# MRCS-MorseKOB_Sounder_Driver.net
KiCad netlist of a schematic drawn in EAGLE
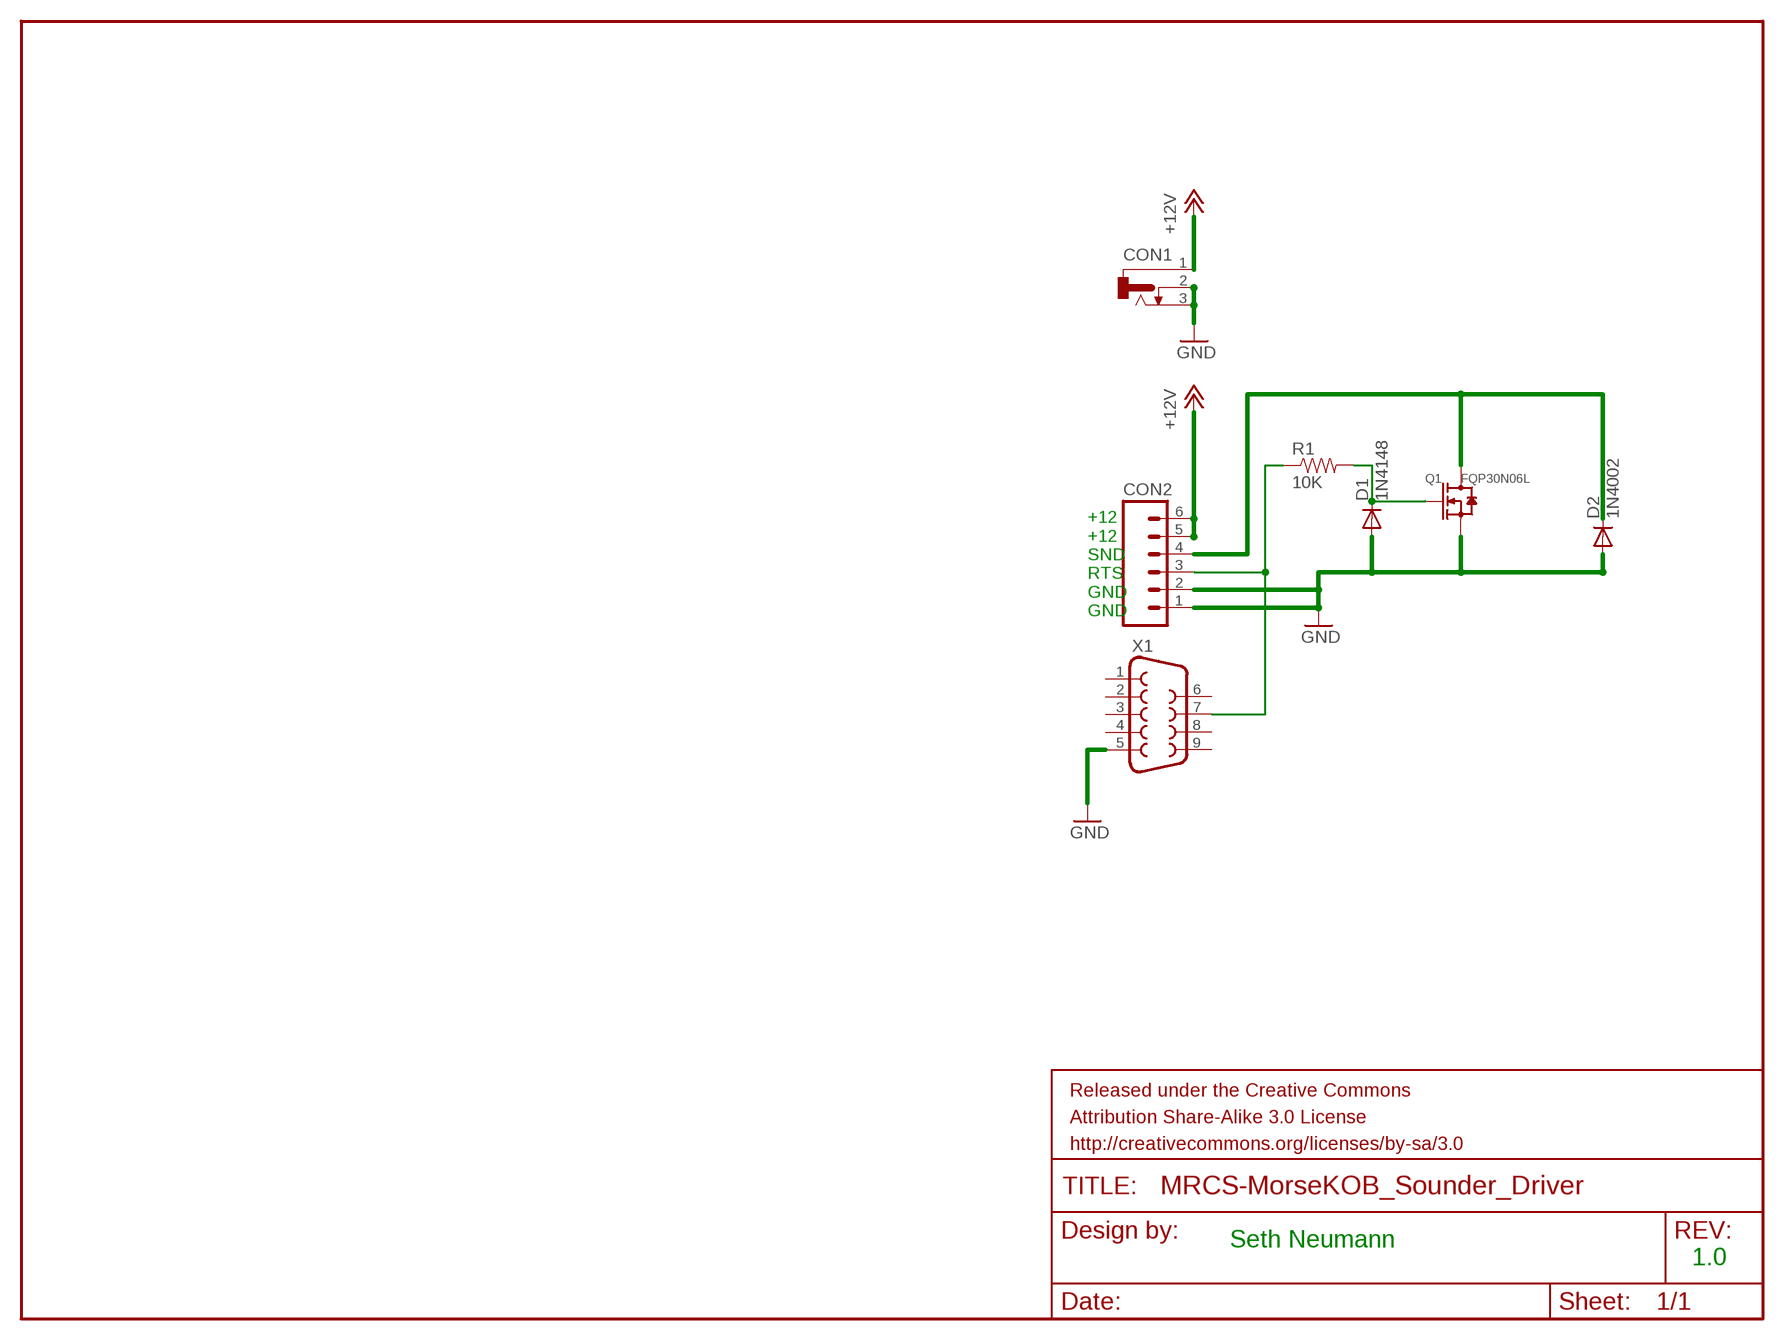
[diagram p0: schematic, sheet 1]

(export (version "E")
  (design (tool "Eeschema 10.0.6"))
  (components
    (comp (ref "CON1")
      (value "CONNECTOR-DC-POWER-RA")
      (footprint "eagle-import:DCJ0202")
      (libsource (lib "eagle-import") (part "CONNECTOR-DC-POWER-RA"))
    )
    (comp (ref "CON2")
      (value "CONNECTOR-M063.5MM-6")
      (footprint "eagle-import:SCREWTERMINAL-3.5MM-6")
      (libsource (lib "eagle-import") (part "CONNECTOR-M063.5MM-6"))
    )
    (comp (ref "D1")
      (value "1N4148")
      (footprint "eagle-import:DIODE-1N4148")
      (libsource (lib "eagle-import") (part "DIODE1N4148"))
    )
    (comp (ref "D2")
      (value "1N4002")
      (footprint "eagle-import:DIODE-1N4001")
      (libsource (lib "eagle-import") (part "DIODEPTH"))
    )
    (comp (ref "FRAME1")
      (value "FRAME-LETTER")
      (footprint "eagle-import:CREATIVE_COMMONS")
      (libsource (lib "eagle-import") (part "FRAME-LETTER"))
    )
    (comp (ref "Q1")
      (value "FQP30N06L")
      (footprint "eagle-import:TO220V")
      (libsource (lib "eagle-import") (part "MOSFET-N--?TO220V"))
    )
    (comp (ref "R1")
      (value "10K")
      (footprint "eagle-import:AXIAL-0.4-RES")
      (libsource (lib "eagle-import") (part "RPTH04"))
    )
    (comp (ref "X1")
      (value "DB9FEMALE")
      (footprint "eagle-import:DB9")
      (libsource (lib "eagle-import") (part "DB9FEMALE"))
    )
  )
  (nets
    (net (code "1") (name "+12V") (class "Default")
      (node (ref "CON1") (pin "1") (pinfunction "1_1") (pintype "passive"))
      (node (ref "CON2") (pin "5") (pinfunction "5_5") (pintype "passive"))
      (node (ref "CON2") (pin "6") (pinfunction "6_6") (pintype "passive"))
    )
    (net (code "2") (name "GND") (class "Default")
      (node (ref "CON1") (pin "2") (pinfunction "2_2") (pintype "passive"))
      (node (ref "CON1") (pin "3") (pinfunction "3_3") (pintype "passive"))
      (node (ref "CON2") (pin "1") (pinfunction "1_1") (pintype "passive"))
      (node (ref "CON2") (pin "2") (pinfunction "2_2") (pintype "passive"))
      (node (ref "D1") (pin "A") (pinfunction "A_A") (pintype "passive"))
      (node (ref "D2") (pin "A") (pinfunction "A_A") (pintype "passive"))
      (node (ref "Q1") (pin "3") (pinfunction "S_3") (pintype "passive"))
      (node (ref "X1") (pin "5") (pinfunction "5_5") (pintype "passive"))
    )
    (net (code "3") (name "Net-(Q1-D)") (class "Default")
      (node (ref "CON2") (pin "4") (pinfunction "4_4") (pintype "passive"))
      (node (ref "D2") (pin "C") (pinfunction "C_C") (pintype "passive"))
      (node (ref "Q1") (pin "2") (pinfunction "D_2") (pintype "passive"))
    )
    (net (code "4") (name "Net-(Q1-G)") (class "Default")
      (node (ref "D1") (pin "C") (pinfunction "C_C") (pintype "passive"))
      (node (ref "Q1") (pin "1") (pinfunction "G_1") (pintype "passive"))
      (node (ref "R1") (pin "P$2") (pinfunction "2_P$2") (pintype "passive"))
    )
    (net (code "5") (name "Net-(R1-1)") (class "Default")
      (node (ref "CON2") (pin "3") (pinfunction "3_3") (pintype "passive"))
      (node (ref "R1") (pin "P$1") (pinfunction "1_P$1") (pintype "passive"))
      (node (ref "X1") (pin "7") (pinfunction "7_7") (pintype "passive"))
    )
    (net (code "6") (name "unconnected-(X1-Pad1)") (class "Default")
      (node (ref "X1") (pin "1") (pinfunction "1_1") (pintype "passive"))
    )
    (net (code "7") (name "unconnected-(X1-Pad2)") (class "Default")
      (node (ref "X1") (pin "2") (pinfunction "2_2") (pintype "passive"))
    )
    (net (code "8") (name "unconnected-(X1-Pad3)") (class "Default")
      (node (ref "X1") (pin "3") (pinfunction "3_3") (pintype "passive"))
    )
    (net (code "9") (name "unconnected-(X1-Pad4)") (class "Default")
      (node (ref "X1") (pin "4") (pinfunction "4_4") (pintype "passive"))
    )
    (net (code "10") (name "unconnected-(X1-Pad6)") (class "Default")
      (node (ref "X1") (pin "6") (pinfunction "6_6") (pintype "passive"))
    )
    (net (code "11") (name "unconnected-(X1-Pad8)") (class "Default")
      (node (ref "X1") (pin "8") (pinfunction "8_8") (pintype "passive"))
    )
    (net (code "12") (name "unconnected-(X1-Pad9)") (class "Default")
      (node (ref "X1") (pin "9") (pinfunction "9_9") (pintype "passive"))
    )
  )
)
